# Uni-2_1_Complete.net
KiCad netlist of a schematic drawn in EAGLE
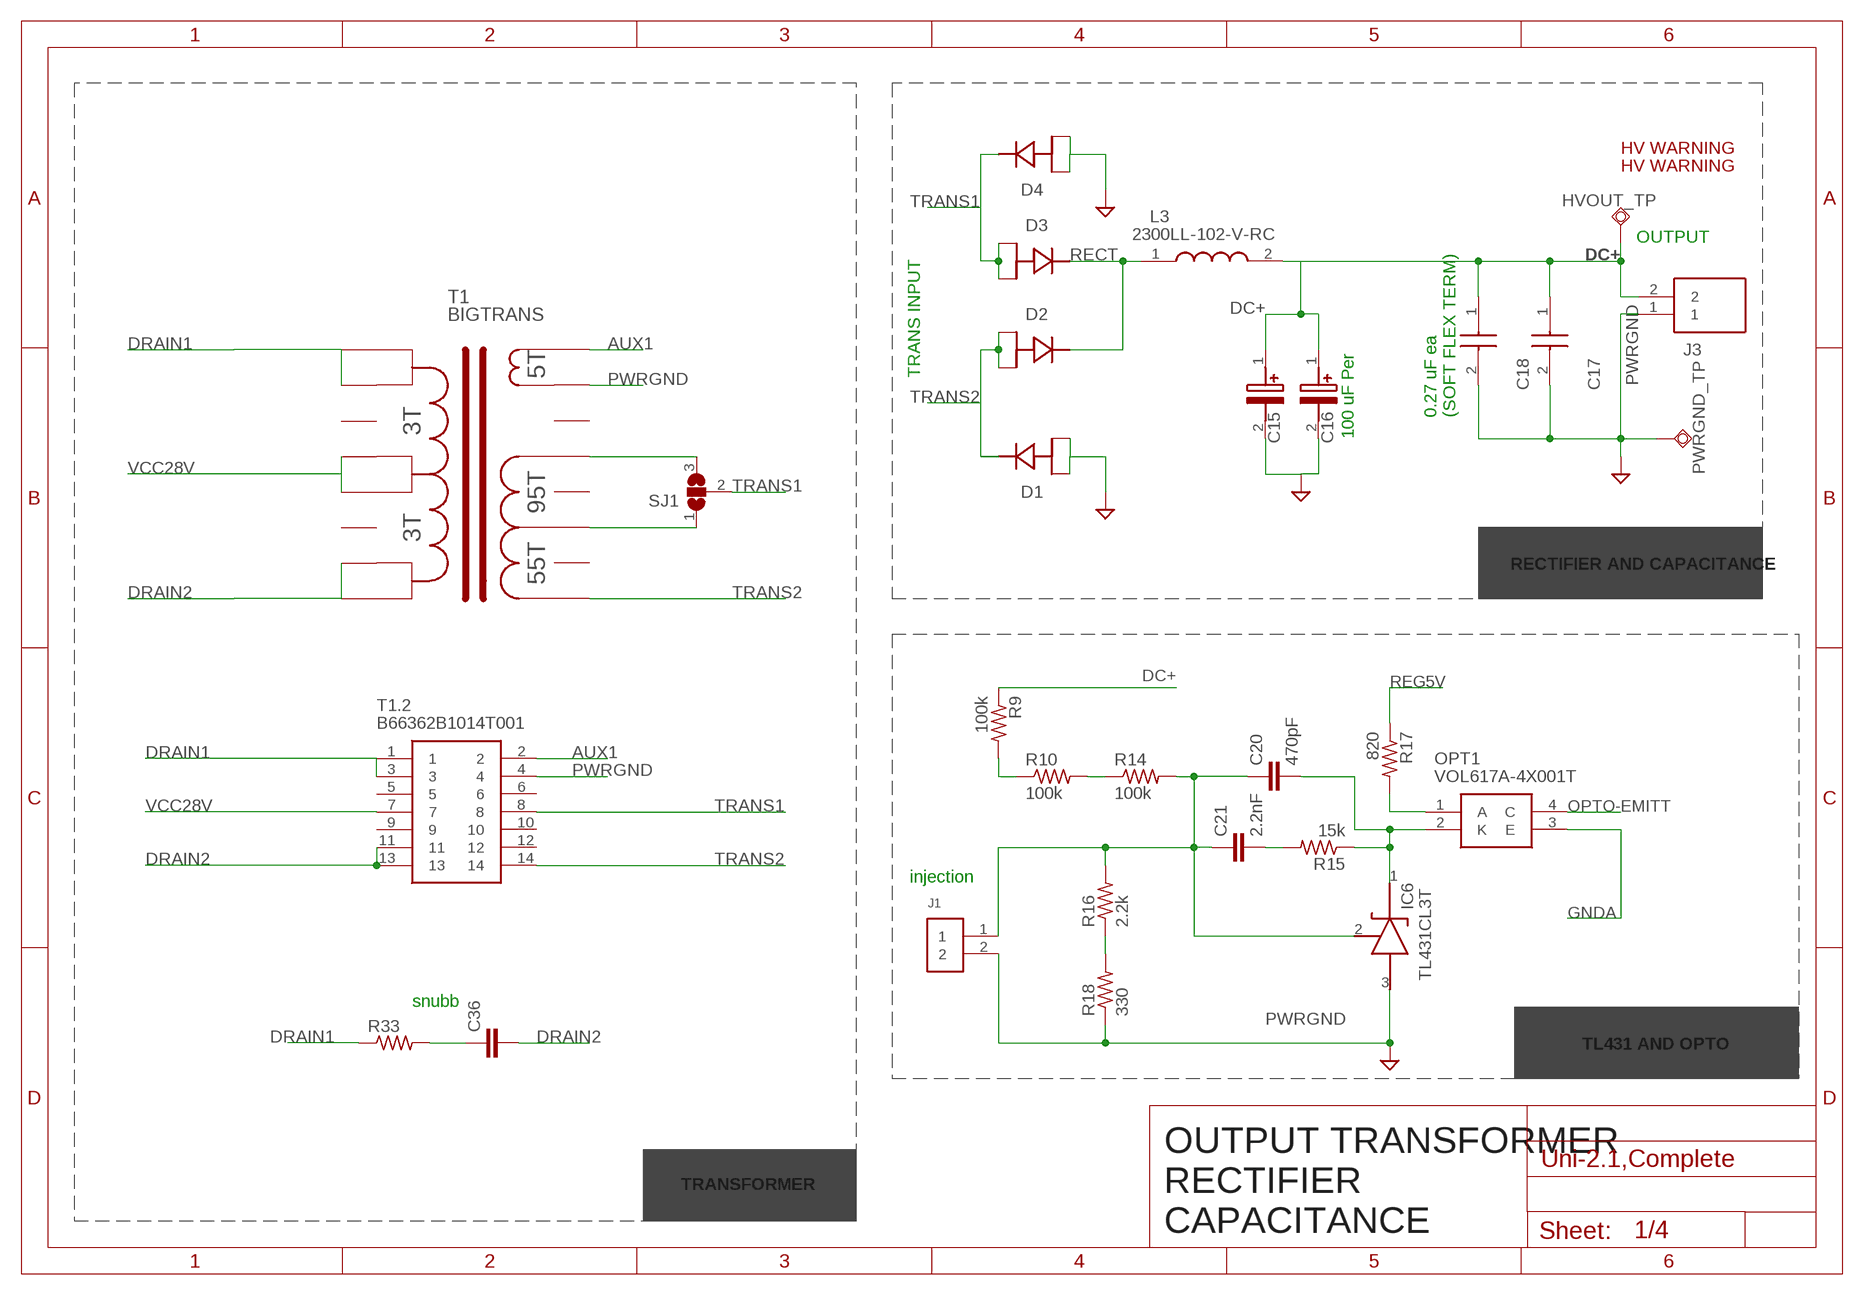
[diagram p0: schematic, sheet 1]
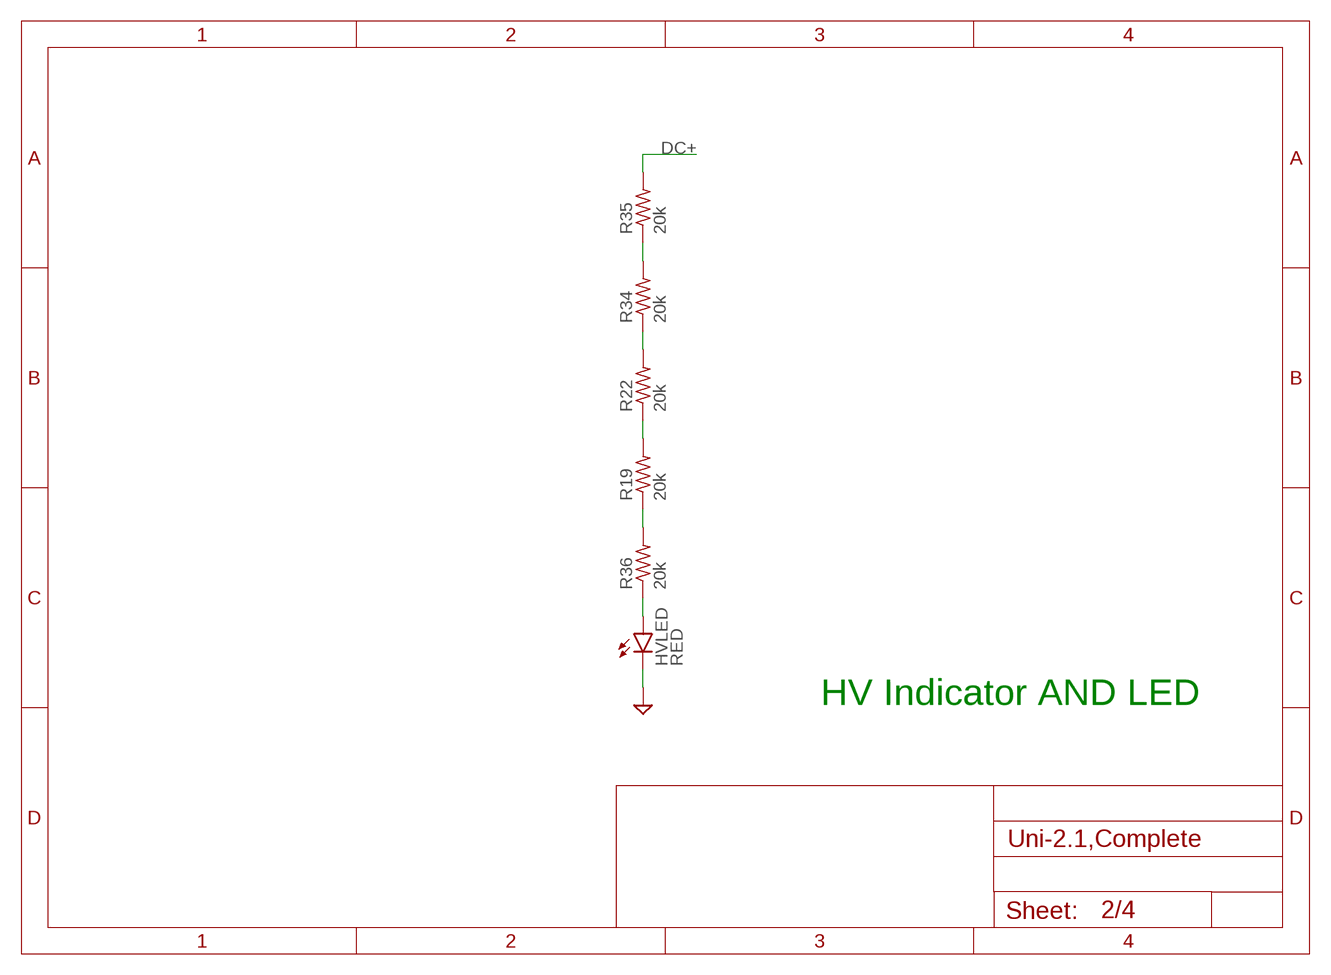
[diagram p1: schematic, sheet 2]
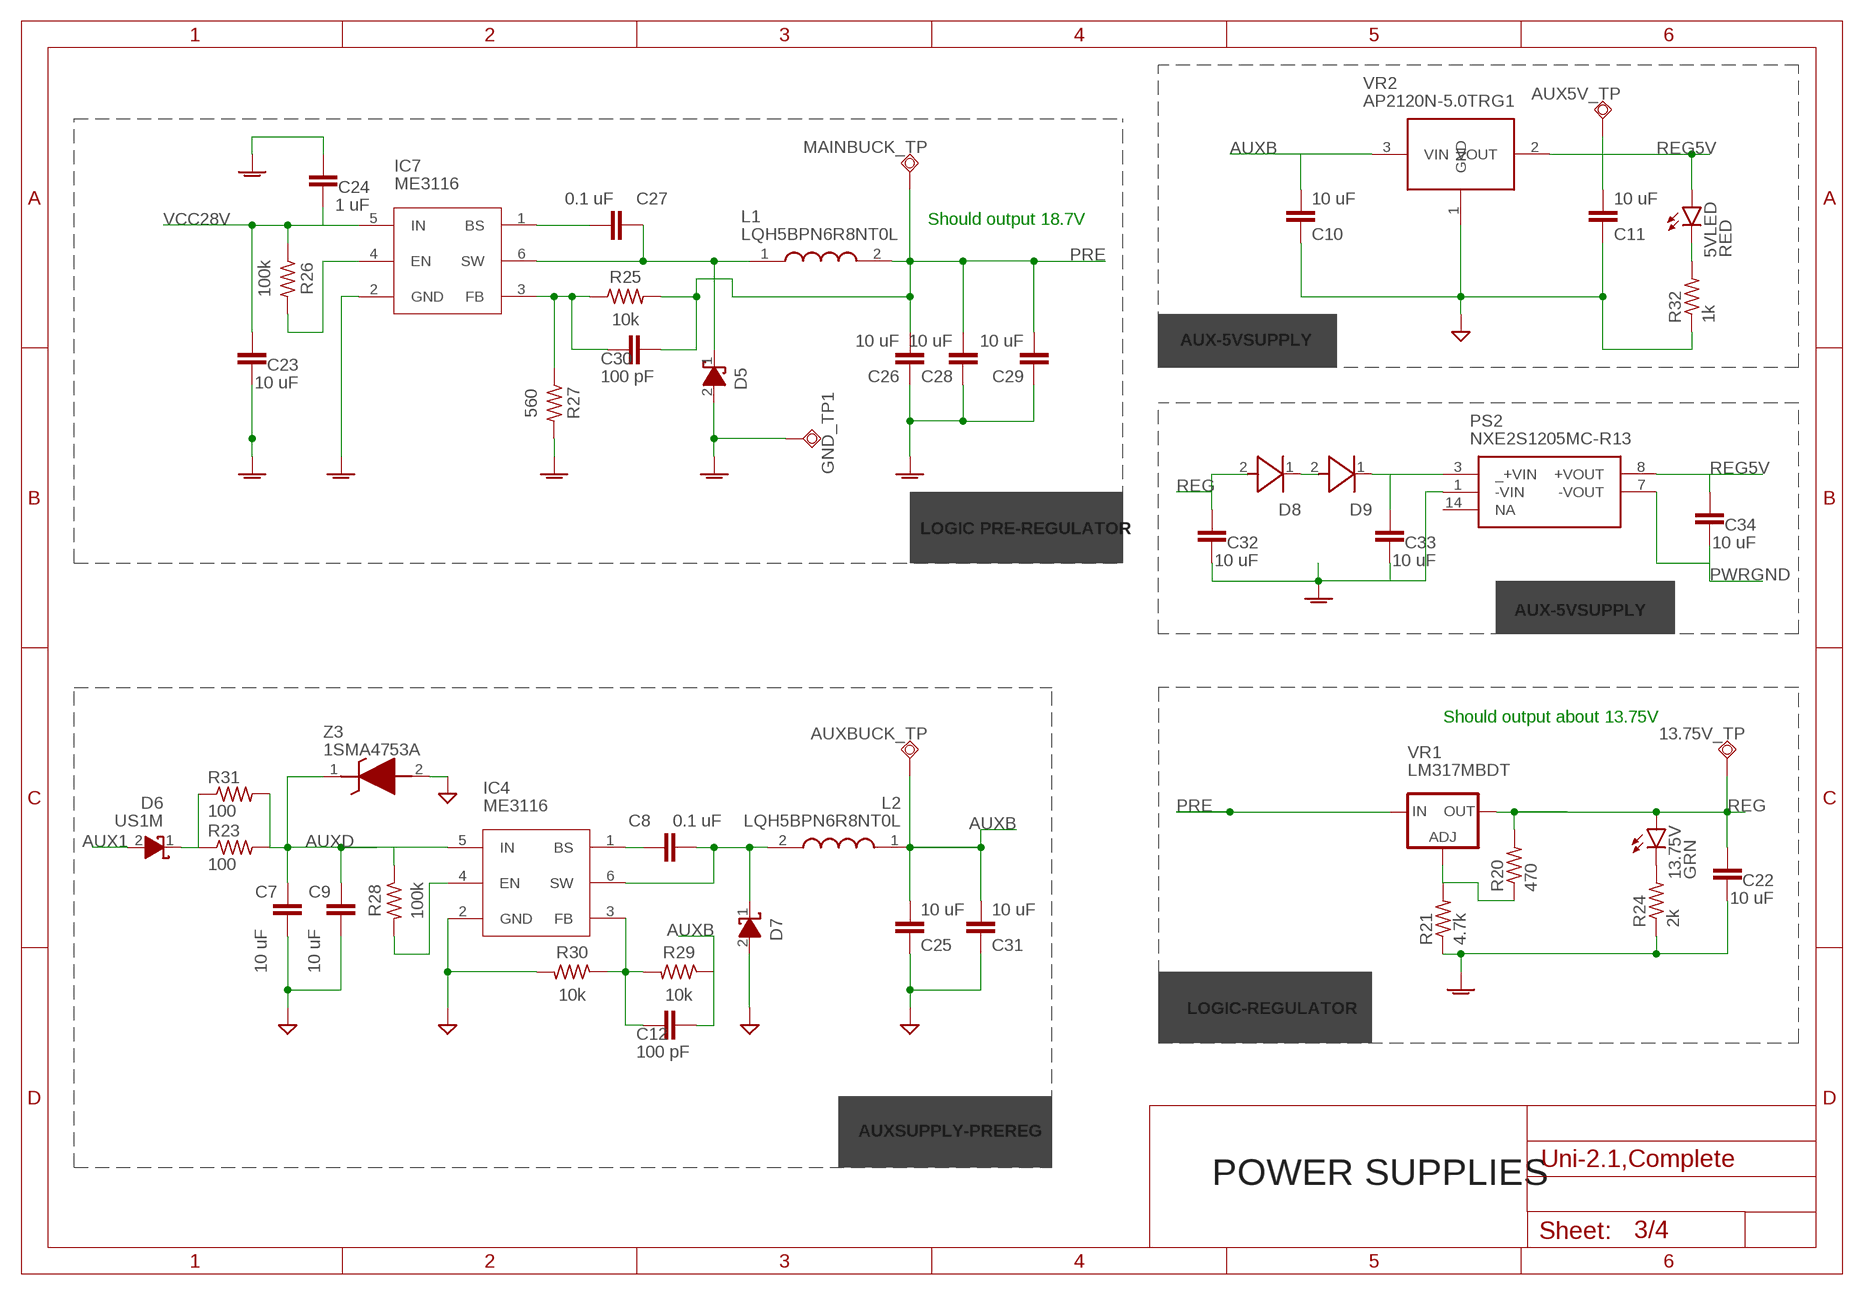
[diagram p2: schematic, sheet 3]
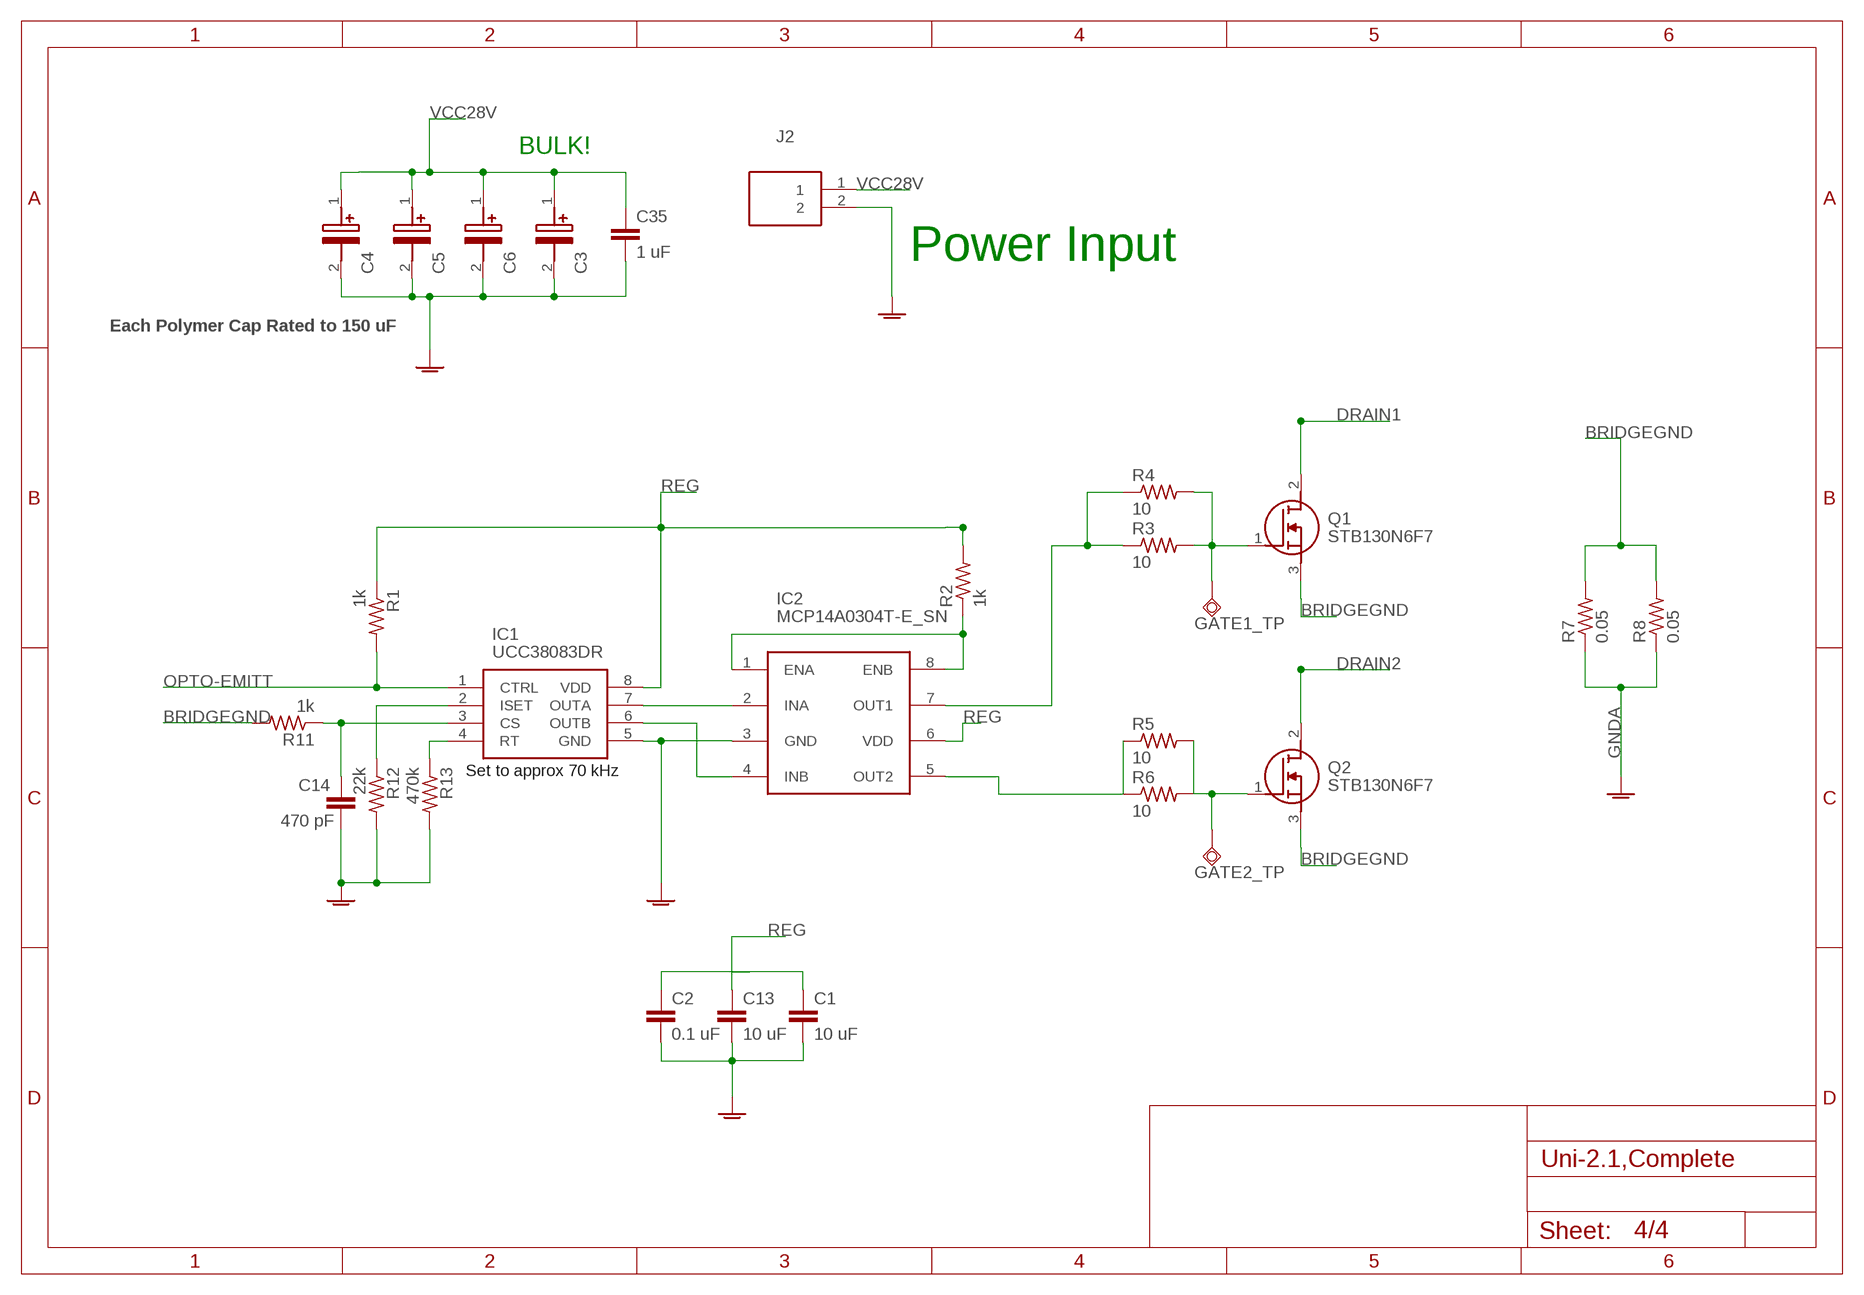
[diagram p3: schematic, sheet 4]

(export (version "E")
  (design (tool "Eeschema 10.0.6"))
  (components
    (comp (ref "C1")
      (value "10 uF")
      (footprint "eagle-import:C0603K")
      (fields (field (name "LCSC_PART") "C440198"))
      (libsource (lib "eagle-import") (part "rcl_334_C-EUC0603K"))
    )
    (comp (ref "C2")
      (value "0.1 uF")
      (footprint "eagle-import:C0603K")
      (fields (field (name "LCSC_PART") "C440198"))
      (libsource (lib "eagle-import") (part "rcl_334_C-EUC0603K"))
    )
    (comp (ref "C3")
      (value "OVK151M1VTR-10131")
      (footprint "eagle-import:16SVF1000M")
      (libsource (lib "eagle-import") (part "OVK151M1VTR-10131"))
    )
    (comp (ref "C4")
      (value "OVK151M1VTR-10131")
      (footprint "eagle-import:16SVF1000M")
      (libsource (lib "eagle-import") (part "OVK151M1VTR-10131"))
    )
    (comp (ref "C5")
      (value "OVK151M1VTR-10131")
      (footprint "eagle-import:16SVF1000M")
      (libsource (lib "eagle-import") (part "OVK151M1VTR-10131"))
    )
    (comp (ref "C6")
      (value "OVK151M1VTR-10131")
      (footprint "eagle-import:16SVF1000M")
      (libsource (lib "eagle-import") (part "OVK151M1VTR-10131"))
    )
    (comp (ref "C13")
      (value "10 uF")
      (footprint "eagle-import:C0603K")
      (fields (field (name "LCSC_PART") "C440198"))
      (libsource (lib "eagle-import") (part "rcl_334_C-EUC0603K"))
    )
    (comp (ref "C14")
      (value "470 pF")
      (footprint "eagle-import:C0603K")
      (fields (field (name "LCSC_PART") "C1620"))
      (libsource (lib "eagle-import") (part "rcl_334_C-EUC0603K"))
    )
    (comp (ref "C35")
      (value "1 uF")
      (footprint "eagle-import:C0805K")
      (fields (field (name "LCSC_PART") "C440198"))
      (libsource (lib "eagle-import") (part "rcl_334_C-EUC0805K"))
    )
    (comp (ref "GATE1_TP")
      (value "TPSQPAD1-17")
      (footprint "eagle-import:P1-17")
      (libsource (lib "eagle-import") (part "TPSQPAD1-17"))
    )
    (comp (ref "GATE2_TP")
      (value "TPSQPAD1-17")
      (footprint "eagle-import:P1-17")
      (libsource (lib "eagle-import") (part "TPSQPAD1-17"))
    )
    (comp (ref "IC1")
      (value "UCC38083DR")
      (footprint "eagle-import:SOIC127P600X175-8N")
      (fields (field (name "MOUSER_PART_NUMBER") "595-UCC38083DR"))
      (libsource (lib "eagle-import") (part "UCC38083DR"))
    )
    (comp (ref "IC2")
      (value "MCP14A0304T-E_SN")
      (footprint "eagle-import:SOIC127P600X175-8N")
      (fields
        (field (name "MANUFACTURER_PART_NUMBER") "MCP14A0304T-E/SN")
        (field (name "MOUSER_PART_NUMBER") "579-MCP14A0304T-E/SN")
      )
      (libsource (lib "eagle-import") (part "MCP14A0304T-E_SN"))
    )
    (comp (ref "J2")
      (value "TB005-762-02BE")
      (footprint "eagle-import:TB00576202BE")
      (fields (field (name "MOUSER_PART_NUMBER") "490-TB005-762-02BE"))
      (libsource (lib "eagle-import") (part "TB005-762-02BE"))
    )
    (comp (ref "Q1")
      (value "STB130N6F7")
      (footprint "eagle-import:D2PAK")
      (libsource (lib "eagle-import") (part "STB130N6F7"))
    )
    (comp (ref "Q2")
      (value "STB130N6F7")
      (footprint "eagle-import:D2PAK")
      (libsource (lib "eagle-import") (part "STB130N6F7"))
    )
    (comp (ref "R1")
      (value "1k")
      (footprint "eagle-import:R0603")
      (fields (field (name "LCSC_PART") "C22975"))
      (libsource (lib "eagle-import") (part "R-US_R0603"))
    )
    (comp (ref "R2")
      (value "1k")
      (footprint "eagle-import:R0402")
      (libsource (lib "eagle-import") (part "R-US_R0402"))
    )
    (comp (ref "R3")
      (value "10")
      (footprint "eagle-import:R0805")
      (libsource (lib "eagle-import") (part "R-US_R0805"))
    )
    (comp (ref "R4")
      (value "10")
      (footprint "eagle-import:R0805")
      (libsource (lib "eagle-import") (part "R-US_R0805"))
    )
    (comp (ref "R5")
      (value "10")
      (footprint "eagle-import:R0805")
      (libsource (lib "eagle-import") (part "R-US_R0805"))
    )
    (comp (ref "R6")
      (value "10")
      (footprint "eagle-import:R0805")
      (libsource (lib "eagle-import") (part "R-US_R0805"))
    )
    (comp (ref "R7")
      (value "0.05")
      (footprint "eagle-import:R2512")
      (libsource (lib "eagle-import") (part "R-US_R2512"))
    )
    (comp (ref "R8")
      (value "0.05")
      (footprint "eagle-import:R2512")
      (libsource (lib "eagle-import") (part "R-US_R2512"))
    )
    (comp (ref "R11")
      (value "1k")
      (footprint "eagle-import:R0603")
      (fields (field (name "LCSC_PART") "C21190"))
      (libsource (lib "eagle-import") (part "R-US_R0603"))
    )
    (comp (ref "R12")
      (value "22k")
      (footprint "eagle-import:R0603")
      (fields (field (name "LCSC_PART") "C31850"))
      (libsource (lib "eagle-import") (part "R-US_R0603"))
    )
    (comp (ref "R13")
      (value "470k")
      (footprint "eagle-import:R0603")
      (fields (field (name "LCSC_PART") "C25811"))
      (libsource (lib "eagle-import") (part "R-US_R0603"))
    )
    (comp (ref "5VLED")
      (value "RED")
      (footprint "eagle-import:CHIPLED_0805")
      (fields (field (name "LCSC_PART") "C72043"))
      (libsource (lib "eagle-import") (part "LEDCHIPLED_0805"))
    )
    (comp (ref "13.75V")
      (value "GRN")
      (footprint "eagle-import:CHIPLED_0805")
      (fields (field (name "LCSC_PART") "C72043"))
      (libsource (lib "eagle-import") (part "LEDCHIPLED_0805"))
    )
    (comp (ref "13.75V_TP")
      (value "TPSQPAD1-17")
      (footprint "eagle-import:P1-17")
      (libsource (lib "eagle-import") (part "TPSQPAD1-17"))
    )
    (comp (ref "AUX5V_TP")
      (value "TPSQPAD1-17")
      (footprint "eagle-import:P1-17")
      (libsource (lib "eagle-import") (part "TPSQPAD1-17"))
    )
    (comp (ref "AUXBUCK_TP")
      (value "TPSQPAD1-17")
      (footprint "eagle-import:P1-17")
      (libsource (lib "eagle-import") (part "TPSQPAD1-17"))
    )
    (comp (ref "C7")
      (value "10 uF")
      (footprint "eagle-import:C0805K")
      (libsource (lib "eagle-import") (part "rcl_334_C-EUC0805K"))
    )
    (comp (ref "C8")
      (value "0.1 uF")
      (footprint "eagle-import:C0603K")
      (fields (field (name "LCSC_PART") "C14663"))
      (libsource (lib "eagle-import") (part "rcl_334_C-EUC0603K"))
    )
    (comp (ref "C9")
      (value "10 uF")
      (footprint "eagle-import:C0805K")
      (libsource (lib "eagle-import") (part "rcl_334_C-EUC0805K"))
    )
    (comp (ref "C10")
      (value "10 uF")
      (footprint "eagle-import:C0603K")
      (fields (field (name "LCSC_PART") "C440198"))
      (libsource (lib "eagle-import") (part "rcl_334_C-EUC0603K"))
    )
    (comp (ref "C11")
      (value "10 uF")
      (footprint "eagle-import:C0603K")
      (libsource (lib "eagle-import") (part "rcl_334_C-EUC0603K"))
    )
    (comp (ref "C12")
      (value "100 pF")
      (footprint "eagle-import:C0402K")
      (fields (field (name "LCSC_PART") "C1546"))
      (libsource (lib "eagle-import") (part "rcl_334_C-EUC0402K"))
    )
    (comp (ref "C22")
      (value "10 uF")
      (footprint "eagle-import:C0805K")
      (fields (field (name "LCSC_PART") "C440198"))
      (libsource (lib "eagle-import") (part "C-EUC0805K"))
    )
    (comp (ref "C23")
      (value "10 uF")
      (footprint "eagle-import:C0805K")
      (fields (field (name "LCSC_PART") "C440198"))
      (libsource (lib "eagle-import") (part "C-EUC0805K"))
    )
    (comp (ref "C24")
      (value "1 uF")
      (footprint "eagle-import:C0603K")
      (fields (field (name "LCSC_PART") "C440198"))
      (libsource (lib "eagle-import") (part "rcl_334_C-EUC0603K"))
    )
    (comp (ref "C25")
      (value "10 uF")
      (footprint "eagle-import:C0603K")
      (fields (field (name "LCSC_PART") "C440198"))
      (libsource (lib "eagle-import") (part "rcl_334_C-EUC0603K"))
    )
    (comp (ref "C26")
      (value "10 uF")
      (footprint "eagle-import:C0805K")
      (fields (field (name "LCSC_PART") "C440198"))
      (libsource (lib "eagle-import") (part "C-EUC0805K"))
    )
    (comp (ref "C27")
      (value "0.1 uF")
      (footprint "eagle-import:C0603K")
      (fields (field (name "LCSC_PART") "C14663"))
      (libsource (lib "eagle-import") (part "rcl_334_C-EUC0603K"))
    )
    (comp (ref "C28")
      (value "10 uF")
      (footprint "eagle-import:C0805K")
      (fields (field (name "LCSC_PART") "C440198"))
      (libsource (lib "eagle-import") (part "C-EUC0805K"))
    )
    (comp (ref "C29")
      (value "10 uF")
      (footprint "eagle-import:C0805K")
      (fields (field (name "LCSC_PART") "C440198"))
      (libsource (lib "eagle-import") (part "C-EUC0805K"))
    )
    (comp (ref "C30")
      (value "100 pF")
      (footprint "eagle-import:C0402K")
      (fields (field (name "LCSC_PART") "C1546"))
      (libsource (lib "eagle-import") (part "rcl_334_C-EUC0402K"))
    )
    (comp (ref "C31")
      (value "10 uF")
      (footprint "eagle-import:C0402")
      (fields (field (name "LCSC_PART") "C440198"))
      (libsource (lib "eagle-import") (part "rcl_334_C-EUC0402"))
    )
    (comp (ref "C32")
      (value "10 uF")
      (footprint "eagle-import:C0805K")
      (fields (field (name "LCSC_PART") "C440198"))
      (libsource (lib "eagle-import") (part "C-EUC0805K"))
    )
    (comp (ref "C33")
      (value "10 uF")
      (footprint "eagle-import:C0603K")
      (fields (field (name "LCSC_PART") "C440198"))
      (libsource (lib "eagle-import") (part "rcl_334_C-EUC0603K"))
    )
    (comp (ref "C34")
      (value "10 uF")
      (footprint "eagle-import:C0603K")
      (fields (field (name "LCSC_PART") "C440198"))
      (libsource (lib "eagle-import") (part "rcl_334_C-EUC0603K"))
    )
    (comp (ref "D5")
      (value "SCHOTTKY")
      (footprint "eagle-import:DIOM5127X229N")
      (fields
        (field (name "MANUFACTURER_PART_NUMBER") "SS16HE3_B/H")
        (field (name "MOUSER_PART_NUMBER") "78-SS16HE3_B/H")
        (field (name "LCSC_PART") "C22452")
      )
      (libsource (lib "eagle-import") (part "SCHOTTKY"))
    )
    (comp (ref "D6")
      (value "US1M")
      (footprint "eagle-import:DIOM5127X229N")
      (fields
        (field (name "MANUFACTURER_PART_NUMBER") "SS16HE3_B/H")
        (field (name "MOUSER_PART_NUMBER") "78-SS16HE3_B/H")
      )
      (libsource (lib "eagle-import") (part "SCHOTTKY"))
    )
    (comp (ref "D7")
      (value "SCHOTTKY")
      (footprint "eagle-import:DIOM5127X229N")
      (fields
        (field (name "MANUFACTURER_PART_NUMBER") "SS16HE3_B/H")
        (field (name "MOUSER_PART_NUMBER") "78-SS16HE3_B/H")
        (field (name "LCSC_PART") "C22452")
      )
      (libsource (lib "eagle-import") (part "SCHOTTKY"))
    )
    (comp (ref "D8")
      (value "SM4007PL")
      (footprint "eagle-import:SOD3716X145N")
      (fields
        (field (name "MANUFACTURER_PART_NUMBER") "1N4148W-7-F")
        (field (name "MOUSER_PART_NUMBER") "621-1N4148W-F")
        (field (name "LCSC_PART") "C64898")
      )
      (libsource (lib "eagle-import") (part "1N4148W-7-F"))
    )
    (comp (ref "D9")
      (value "SM4007PL")
      (footprint "eagle-import:SOD3716X145N")
      (fields
        (field (name "MANUFACTURER_PART_NUMBER") "1N4148W-7-F")
        (field (name "MOUSER_PART_NUMBER") "621-1N4148W-F")
        (field (name "LCSC_PART") "C64898")
      )
      (libsource (lib "eagle-import") (part "1N4148W-7-F"))
    )
    (comp (ref "GND_TP1")
      (value "TPSQPAD1-13")
      (footprint "eagle-import:P1-13")
      (libsource (lib "eagle-import") (part "TPSQPAD1-13"))
    )
    (comp (ref "IC4")
      (value "ME3116")
      (footprint "eagle-import:SOT95P280X100-6N")
      (fields (field (name "LCSC_PART") "C97643"))
      (libsource (lib "eagle-import") (part "ME3116"))
    )
    (comp (ref "IC7")
      (value "ME3116")
      (footprint "eagle-import:SOT95P280X100-6N")
      (fields (field (name "LCSC_PART") "C97643"))
      (libsource (lib "eagle-import") (part "ME3116"))
    )
    (comp (ref "L1")
      (value "LQH5BPN6R8NT0L")
      (footprint "eagle-import:LQH5BPB100MT0L")
      (fields (field (name "MOUSER_PART_NUMBER") "81-LQH5BPN6R8NT0L0L"))
      (libsource (lib "eagle-import") (part "LQH5BPN6R8NT0L"))
    )
    (comp (ref "L2")
      (value "LQH5BPN6R8NT0L")
      (footprint "eagle-import:LQH5BPB100MT0L")
      (fields (field (name "MOUSER_PART_NUMBER") "81-LQH5BPN6R8NT0L0L"))
      (libsource (lib "eagle-import") (part "LQH5BPN6R8NT0L"))
    )
    (comp (ref "MAINBUCK_TP")
      (value "TPSQPAD1-17")
      (footprint "eagle-import:P1-17")
      (libsource (lib "eagle-import") (part "TPSQPAD1-17"))
    )
    (comp (ref "PS2")
      (value "NXE2S1205MC-R13")
      (footprint "eagle-import:NXE2S1205MCR13")
      (fields (field (name "MOUSER_PART_NUMBER") "580-NXE2S1205MC-R13"))
      (libsource (lib "eagle-import") (part "NXE2S1205MC-R13"))
    )
    (comp (ref "R20")
      (value "470")
      (footprint "eagle-import:R0603")
      (fields (field (name "LCSC_PART") "C22975"))
      (libsource (lib "eagle-import") (part "R-US_R0603"))
    )
    (comp (ref "R21")
      (value "4.7k")
      (footprint "eagle-import:R0603")
      (fields (field (name "LCSC_PART") "C22975"))
      (libsource (lib "eagle-import") (part "R-US_R0603"))
    )
    (comp (ref "R23")
      (value "100")
      (footprint "eagle-import:R1206")
      (libsource (lib "eagle-import") (part "R-US_R1206"))
    )
    (comp (ref "R24")
      (value "2k")
      (footprint "eagle-import:R0603")
      (fields (field (name "LCSC_PART") "C22975"))
      (libsource (lib "eagle-import") (part "R-US_R0603"))
    )
    (comp (ref "R25")
      (value "10k")
      (footprint "eagle-import:R0402")
      (fields (field (name "LCSC_PART") "C25779"))
      (libsource (lib "eagle-import") (part "R-US_R0402"))
    )
    (comp (ref "R26")
      (value "100k")
      (footprint "eagle-import:R0402")
      (fields (field (name "LCSC_PART") "C25741") (field (name "SPICEPREFIX") "R"))
      (libsource (lib "eagle-import") (part "R-US_R0402"))
    )
    (comp (ref "R27")
      (value "560")
      (footprint "eagle-import:R0402")
      (fields (field (name "LCSC_PART") "C4177") (field (name "SPICEPREFIX") "R"))
      (libsource (lib "eagle-import") (part "R-US_R0402"))
    )
    (comp (ref "R28")
      (value "100k")
      (footprint "eagle-import:R0402")
      (fields (field (name "LCSC_PART") "C25741") (field (name "SPICEPREFIX") "R"))
      (libsource (lib "eagle-import") (part "R-US_R0402"))
    )
    (comp (ref "R29")
      (value "10k")
      (footprint "eagle-import:R0402")
      (fields (field (name "LCSC_PART") "C25779"))
      (libsource (lib "eagle-import") (part "R-US_R0402"))
    )
    (comp (ref "R30")
      (value "10k")
      (footprint "eagle-import:R0402")
      (fields (field (name "LCSC_PART") "C25779"))
      (libsource (lib "eagle-import") (part "R-US_R0402"))
    )
    (comp (ref "R31")
      (value "100")
      (footprint "eagle-import:R1206")
      (libsource (lib "eagle-import") (part "R-US_R1206"))
    )
    (comp (ref "R32")
      (value "1k")
      (footprint "eagle-import:R0603")
      (fields (field (name "LCSC_PART") "C22975"))
      (libsource (lib "eagle-import") (part "R-US_R0603"))
    )
    (comp (ref "VR1")
      (value "LM317MBDT")
      (footprint "eagle-import:DPACK")
      (libsource (lib "eagle-import") (part "LM317?MBDT"))
    )
    (comp (ref "VR2")
      (value "AP2120N-5.0TRG1")
      (footprint "eagle-import:SOT95P240X120-3N")
      (fields (field (name "MOUSER_PART_NUMBER") "621-AP2120N-5.0TRG1"))
      (libsource (lib "eagle-import") (part "AP2120N-5.0TRG1"))
    )
    (comp (ref "Z3")
      (value "1SMA4753A")
      (footprint "eagle-import:DIOM5226X220N")
      (fields
        (field (name "MANUFACTURER_PART_NUMBER") "1SMA5942BT3G")
        (field (name "MOUSER_PART_NUMBER") "863-1SMA5942BT3G")
        (field (name "LCSC_PART") "C362284")
      )
      (libsource (lib "eagle-import") (part "1SMA5942BT3G"))
    )
    (comp (ref "C15")
      (value "400BXW100MEFR18X25")
      (footprint "eagle-import:CAPPRD750W80D1825H2700")
      (libsource (lib "eagle-import") (part "400BXW100MEFR18X25"))
    )
    (comp (ref "C16")
      (value "400BXW100MEFR18X25")
      (footprint "eagle-import:CAPPRD750W80D1825H2700")
      (libsource (lib "eagle-import") (part "400BXW100MEFR18X25"))
    )
    (comp (ref "C17")
      (value "C1812C274KCRACAUTO")
      (footprint "eagle-import:C1812")
      (fields (field (name "MOUSER_PART_NUMBER") "80-C1812C274KCRAUTO"))
      (libsource (lib "eagle-import") (part "C1812C274KCRACAUTO"))
    )
    (comp (ref "C18")
      (value "C1812C274KCRACAUTO")
      (footprint "eagle-import:C1812")
      (fields (field (name "MOUSER_PART_NUMBER") "80-C1812C274KCRAUTO"))
      (libsource (lib "eagle-import") (part "C1812C274KCRACAUTO"))
    )
    (comp (ref "C20")
      (value "470pF")
      (footprint "eagle-import:C0603K")
      (libsource (lib "eagle-import") (part "rcl_334_C-EUC0603K"))
    )
    (comp (ref "C21")
      (value "2.2nF")
      (footprint "eagle-import:C0603K")
      (libsource (lib "eagle-import") (part "rcl_334_C-EUC0603K"))
    )
    (comp (ref "C36")
      (value "C-EUC1210K")
      (footprint "eagle-import:C1210K")
      (libsource (lib "eagle-import") (part "rcl_334_C-EUC1210K"))
    )
    (comp (ref "D1")
      (value "FERD20H60CG-TR")
      (footprint "eagle-import:STB20N95K5")
      (fields (field (name "MOUSER_PART_NUMBER") "511-FERD20H60CG-TR"))
      (libsource (lib "eagle-import") (part "FERD20H60CG-TR"))
    )
    (comp (ref "D2")
      (value "FERD20H60CG-TR")
      (footprint "eagle-import:STB20N95K5")
      (fields (field (name "MOUSER_PART_NUMBER") "511-FERD20H60CG-TR"))
      (libsource (lib "eagle-import") (part "FERD20H60CG-TR"))
    )
    (comp (ref "D3")
      (value "FERD20H60CG-TR")
      (footprint "eagle-import:STB20N95K5")
      (fields (field (name "MOUSER_PART_NUMBER") "511-FERD20H60CG-TR"))
      (libsource (lib "eagle-import") (part "FERD20H60CG-TR"))
    )
    (comp (ref "D4")
      (value "FERD20H60CG-TR")
      (footprint "eagle-import:STB20N95K5")
      (fields (field (name "MOUSER_PART_NUMBER") "511-FERD20H60CG-TR"))
      (libsource (lib "eagle-import") (part "FERD20H60CG-TR"))
    )
    (comp (ref "HVOUT_TP")
      (value "TPSQPAD1-13")
      (footprint "eagle-import:P1-13")
      (libsource (lib "eagle-import") (part "TPSQPAD1-13"))
    )
    (comp (ref "IC6")
      (value "TL431CL3T")
      (footprint "eagle-import:SOT95P237X112-3N")
      (fields (field (name "MOUSER_PART_NUMBER") "511-TL431CL3T"))
      (libsource (lib "eagle-import") (part "TL431CL3T"))
    )
    (comp (ref "J1")
      (value "61300211121")
      (footprint "eagle-import:61300211121")
      (fields
        (field (name "DIGI_KEY_PART_NUMBER") "732-5315-ND")
        (field (name "MANUFACTURER") "Wurth Electronics Inc.")
        (field (name "CREATED_BY") "PCBLayout.com")
      )
      (libsource (lib "eagle-import") (part "61300211121"))
    )
    (comp (ref "J3")
      (value "TB005-762-02BE")
      (footprint "eagle-import:TB00576202BE")
      (fields (field (name "MOUSER_PART_NUMBER") "490-TB005-762-02BE"))
      (libsource (lib "eagle-import") (part "TB005-762-02BE"))
    )
    (comp (ref "L3")
      (value "2300LL-102-V-RC")
      (footprint "eagle-import:2300LL102VRC")
      (fields (field (name "MOUSER_PART_NUMBER") "652-2300LL-102-V-RC"))
      (libsource (lib "eagle-import") (part "2300LL-102-V-RC"))
    )
    (comp (ref "OPT1")
      (value "VOL617A-4X001T")
      (footprint "eagle-import:SOP254P1015X230-4N")
      (fields (field (name "MOUSER_PART_NUMBER") "78-VOL617A-4X001T"))
      (libsource (lib "eagle-import") (part "VOL617A-4X001T"))
    )
    (comp (ref "PWRGND_TP")
      (value "TPSQPAD1-13")
      (footprint "eagle-import:P1-13")
      (libsource (lib "eagle-import") (part "TPSQPAD1-13"))
    )
    (comp (ref "R9")
      (value "100k")
      (footprint "eagle-import:R1206")
      (libsource (lib "eagle-import") (part "R-US_R1206"))
    )
    (comp (ref "R10")
      (value "100k")
      (footprint "eagle-import:R1206")
      (libsource (lib "eagle-import") (part "R-US_R1206"))
    )
    (comp (ref "R14")
      (value "100k")
      (footprint "eagle-import:R1206")
      (libsource (lib "eagle-import") (part "R-US_R1206"))
    )
    (comp (ref "R15")
      (value "15k")
      (footprint "eagle-import:R0603")
      (libsource (lib "eagle-import") (part "R-US_R0603"))
    )
    (comp (ref "R16")
      (value "2.2k")
      (footprint "eagle-import:R0805")
      (libsource (lib "eagle-import") (part "R-US_R0805"))
    )
    (comp (ref "R17")
      (value "820")
      (footprint "eagle-import:R0603")
      (libsource (lib "eagle-import") (part "R-US_R0603"))
    )
    (comp (ref "R18")
      (value "330")
      (footprint "eagle-import:R0805")
      (libsource (lib "eagle-import") (part "R-US_R0805"))
    )
    (comp (ref "R33")
      (value "R-US_R1206")
      (footprint "eagle-import:R1206")
      (libsource (lib "eagle-import") (part "R-US_R1206"))
    )
    (comp (ref "SJ1")
      (value "SJ2WW")
      (footprint "eagle-import:SJ_2W")
      (libsource (lib "eagle-import") (part "SJ2WW"))
    )
    (comp (ref "T1")
      (value "BIGTRANS")
      (footprint "eagle-import:BIGTRANS!")
      (libsource (lib "eagle-import") (part "BIGTRANS"))
    )
    (comp (ref "T1.2")
      (value "B66362B1014T001")
      (footprint "eagle-import:B66362B1014T001")
      (fields (field (name "MOUSER_PART_NUMBER") "871-B66362B1014T001"))
      (libsource (lib "eagle-import") (part "B66362B1014T001"))
    )
    (comp (ref "U$2")
      (value "HV")
      (footprint "eagle-import:PSFBC_ELECTRIC_SHOCK")
      (libsource (lib "eagle-import") (part "HV"))
    )
    (comp (ref "U$3")
      (value "HV")
      (footprint "eagle-import:PSFBC_ELECTRIC_SHOCK")
      (libsource (lib "eagle-import") (part "HV"))
    )
    (comp (ref "HVLED")
      (value "RED")
      (footprint "eagle-import:CHIPLED_0805")
      (libsource (lib "eagle-import") (part "LEDCHIPLED_0805"))
    )
    (comp (ref "R19")
      (value "20k")
      (footprint "eagle-import:R1206")
      (libsource (lib "eagle-import") (part "R-US_R1206"))
    )
    (comp (ref "R22")
      (value "20k")
      (footprint "eagle-import:R1206")
      (libsource (lib "eagle-import") (part "R-US_R1206"))
    )
    (comp (ref "R34")
      (value "20k")
      (footprint "eagle-import:R1206")
      (libsource (lib "eagle-import") (part "R-US_R1206"))
    )
    (comp (ref "R35")
      (value "20k")
      (footprint "eagle-import:R1206")
      (libsource (lib "eagle-import") (part "R-US_R1206"))
    )
    (comp (ref "R36")
      (value "20k")
      (footprint "eagle-import:R1206")
      (libsource (lib "eagle-import") (part "R-US_R1206"))
    )
  )
  (nets
    (net (code "1") (name "AUX1") (class "Default")
      (node (ref "D6") (pin "2") (pinfunction "A_2") (pintype "bidirectional"))
      (node (ref "T1") (pin "16") (pinfunction "16_16") (pintype "bidirectional"))
      (node (ref "T1.2") (pin "2") (pinfunction "2_2") (pintype "bidirectional"))
    )
    (net (code "2") (name "AUXB") (class "Default")
      (node (ref "AUXBUCK_TP") (pin "TP") (pinfunction "TP_TP") (pintype "input"))
      (node (ref "C10") (pin "2") (pinfunction "2_2") (pintype "passive"))
      (node (ref "C12") (pin "1") (pinfunction "1_1") (pintype "passive"))
      (node (ref "C25") (pin "2") (pinfunction "2_2") (pintype "passive"))
      (node (ref "C31") (pin "2") (pinfunction "2_2") (pintype "passive"))
      (node (ref "L2") (pin "1") (pinfunction "1_1") (pintype "bidirectional"))
      (node (ref "R29") (pin "1") (pinfunction "1_1") (pintype "passive"))
      (node (ref "VR2") (pin "3") (pinfunction "VIN_3") (pintype "bidirectional"))
    )
    (net (code "3") (name "AUXD") (class "Default")
      (node (ref "C7") (pin "1") (pinfunction "1_1") (pintype "passive"))
      (node (ref "C9") (pin "1") (pinfunction "1_1") (pintype "passive"))
      (node (ref "IC4") (pin "5") (pinfunction "IN_5") (pintype "bidirectional"))
      (node (ref "R23") (pin "2") (pinfunction "2_2") (pintype "passive"))
      (node (ref "R28") (pin "1") (pinfunction "1_1") (pintype "passive"))
      (node (ref "R31") (pin "2") (pinfunction "2_2") (pintype "passive"))
      (node (ref "Z3") (pin "1") (pinfunction "K_1") (pintype "bidirectional"))
    )
    (net (code "4") (name "BRIDGEGND") (class "Default")
      (node (ref "Q1") (pin "3") (pinfunction "S_3") (pintype "bidirectional"))
      (node (ref "Q2") (pin "3") (pinfunction "S_3") (pintype "bidirectional"))
      (node (ref "R11") (pin "2") (pinfunction "2_2") (pintype "passive"))
      (node (ref "R7") (pin "2") (pinfunction "2_2") (pintype "passive"))
      (node (ref "R8") (pin "2") (pinfunction "2_2") (pintype "passive"))
    )
    (net (code "5") (name "DC+") (class "Default")
      (node (ref "C15") (pin "1") (pinfunction "+_1") (pintype "bidirectional"))
      (node (ref "C16") (pin "1") (pinfunction "+_1") (pintype "bidirectional"))
      (node (ref "C17") (pin "1") (pinfunction "1_1") (pintype "bidirectional"))
      (node (ref "C18") (pin "1") (pinfunction "1_1") (pintype "bidirectional"))
      (node (ref "HVOUT_TP") (pin "TP") (pinfunction "TP_TP") (pintype "input"))
      (node (ref "J3") (pin "2") (pinfunction "2_2") (pintype "bidirectional"))
      (node (ref "L3") (pin "2") (pinfunction "2_2") (pintype "bidirectional"))
      (node (ref "R35") (pin "2") (pinfunction "2_2") (pintype "passive"))
      (node (ref "R9") (pin "1") (pinfunction "1_1") (pintype "passive"))
    )
    (net (code "6") (name "DRAIN1") (class "Default")
      (node (ref "Q1") (pin "2") (pinfunction "D_2") (pintype "bidirectional"))
      (node (ref "R33") (pin "1") (pinfunction "1_1") (pintype "passive"))
      (node (ref "T1") (pin "7") (pinfunction "7_7") (pintype "bidirectional"))
      (node (ref "T1") (pin "8") (pinfunction "8_8") (pintype "bidirectional"))
      (node (ref "T1.2") (pin "1") (pinfunction "1_1") (pintype "bidirectional"))
      (node (ref "T1.2") (pin "3") (pinfunction "3_3") (pintype "bidirectional"))
    )
    (net (code "7") (name "DRAIN2") (class "Default")
      (node (ref "C36") (pin "2") (pinfunction "2_2") (pintype "passive"))
      (node (ref "Q2") (pin "2") (pinfunction "D_2") (pintype "bidirectional"))
      (node (ref "T1") (pin "1") (pinfunction "1_1") (pintype "bidirectional"))
      (node (ref "T1") (pin "2") (pinfunction "2_2") (pintype "bidirectional"))
      (node (ref "T1.2") (pin "11") (pinfunction "11_11") (pintype "bidirectional"))
      (node (ref "T1.2") (pin "13") (pinfunction "13_13") (pintype "bidirectional"))
    )
    (net (code "8") (name "GNDA") (class "Default")
      (node (ref "C1") (pin "2") (pinfunction "2_2") (pintype "passive"))
      (node (ref "C13") (pin "2") (pinfunction "2_2") (pintype "passive"))
      (node (ref "C14") (pin "2") (pinfunction "2_2") (pintype "passive"))
      (node (ref "C2") (pin "2") (pinfunction "2_2") (pintype "passive"))
      (node (ref "C22") (pin "1") (pinfunction "1_1") (pintype "passive"))
      (node (ref "C23") (pin "1") (pinfunction "1_1") (pintype "passive"))
      (node (ref "C24") (pin "2") (pinfunction "2_2") (pintype "passive"))
      (node (ref "C26") (pin "1") (pinfunction "1_1") (pintype "passive"))
      (node (ref "C28") (pin "1") (pinfunction "1_1") (pintype "passive"))
      (node (ref "C29") (pin "1") (pinfunction "1_1") (pintype "passive"))
      (node (ref "C3") (pin "2") (pinfunction "-_2") (pintype "bidirectional"))
      (node (ref "C32") (pin "1") (pinfunction "1_1") (pintype "passive"))
      (node (ref "C33") (pin "1") (pinfunction "1_1") (pintype "passive"))
      (node (ref "C35") (pin "2") (pinfunction "2_2") (pintype "passive"))
      (node (ref "C4") (pin "2") (pinfunction "-_2") (pintype "bidirectional"))
      (node (ref "C5") (pin "2") (pinfunction "-_2") (pintype "bidirectional"))
      (node (ref "C6") (pin "2") (pinfunction "-_2") (pintype "bidirectional"))
      (node (ref "D5") (pin "2") (pinfunction "A_2") (pintype "bidirectional"))
      (node (ref "GND_TP1") (pin "TP") (pinfunction "TP_TP") (pintype "input"))
      (node (ref "IC1") (pin "5") (pinfunction "GND_5") (pintype "bidirectional"))
      (node (ref "IC2") (pin "3") (pinfunction "GND_3") (pintype "bidirectional"))
      (node (ref "IC7") (pin "2") (pinfunction "GND_2") (pintype "bidirectional"))
      (node (ref "J2") (pin "2") (pinfunction "2_2") (pintype "bidirectional"))
      (node (ref "OPT1") (pin "3") (pinfunction "E_3") (pintype "bidirectional"))
      (node (ref "PS2") (pin "1") (pinfunction "-VIN_1") (pintype "bidirectional"))
      (node (ref "R12") (pin "2") (pinfunction "2_2") (pintype "passive"))
      (node (ref "R13") (pin "2") (pinfunction "2_2") (pintype "passive"))
      (node (ref "R21") (pin "1") (pinfunction "1_1") (pintype "passive"))
      (node (ref "R24") (pin "1") (pinfunction "1_1") (pintype "passive"))
      (node (ref "R27") (pin "2") (pinfunction "2_2") (pintype "passive"))
      (node (ref "R7") (pin "1") (pinfunction "1_1") (pintype "passive"))
      (node (ref "R8") (pin "1") (pinfunction "1_1") (pintype "passive"))
    )
    (net (code "9") (name "Net-(5VLED-PadC)") (class "Default")
      (node (ref "5VLED") (pin "C") (pinfunction "C_C") (pintype "passive"))
      (node (ref "R32") (pin "2") (pinfunction "2_2") (pintype "passive"))
    )
    (net (code "10") (name "Net-(13.75V-PadC)") (class "Default")
      (node (ref "13.75V") (pin "C") (pinfunction "C_C") (pintype "passive"))
      (node (ref "R24") (pin "2") (pinfunction "2_2") (pintype "passive"))
    )
    (net (code "11") (name "Net-(C21-Pad2)") (class "Default")
      (node (ref "C21") (pin "2") (pinfunction "2_2") (pintype "passive"))
      (node (ref "R15") (pin "2") (pinfunction "2_2") (pintype "passive"))
    )
    (net (code "12") (name "Net-(C36-Pad1)") (class "Default")
      (node (ref "C36") (pin "1") (pinfunction "1_1") (pintype "passive"))
      (node (ref "R33") (pin "2") (pinfunction "2_2") (pintype "passive"))
    )
    (net (code "13") (name "Net-(D5-K)") (class "Default")
      (node (ref "C27") (pin "1") (pinfunction "1_1") (pintype "passive"))
      (node (ref "D5") (pin "1") (pinfunction "K_1") (pintype "bidirectional"))
      (node (ref "IC7") (pin "6") (pinfunction "SW_6") (pintype "bidirectional"))
      (node (ref "L1") (pin "1") (pinfunction "1_1") (pintype "bidirectional"))
    )
    (net (code "14") (name "Net-(D6-K)") (class "Default")
      (node (ref "D6") (pin "1") (pinfunction "K_1") (pintype "bidirectional"))
      (node (ref "R23") (pin "1") (pinfunction "1_1") (pintype "passive"))
      (node (ref "R31") (pin "1") (pinfunction "1_1") (pintype "passive"))
    )
    (net (code "15") (name "Net-(D7-K)") (class "Default")
      (node (ref "C8") (pin "2") (pinfunction "2_2") (pintype "passive"))
      (node (ref "D7") (pin "1") (pinfunction "K_1") (pintype "bidirectional"))
      (node (ref "IC4") (pin "6") (pinfunction "SW_6") (pintype "bidirectional"))
      (node (ref "L2") (pin "2") (pinfunction "2_2") (pintype "bidirectional"))
    )
    (net (code "16") (name "Net-(D8-K)") (class "Default")
      (node (ref "D8") (pin "1") (pinfunction "K_1") (pintype "bidirectional"))
      (node (ref "D9") (pin "2") (pinfunction "A_2") (pintype "bidirectional"))
    )
    (net (code "17") (name "Net-(D9-K)") (class "Default")
      (node (ref "C33") (pin "2") (pinfunction "2_2") (pintype "passive"))
      (node (ref "D9") (pin "1") (pinfunction "K_1") (pintype "bidirectional"))
      (node (ref "PS2") (pin "3") (pinfunction "_+VIN_3") (pintype "bidirectional"))
    )
    (net (code "18") (name "Net-(HVLED-PadA)") (class "Default")
      (node (ref "HVLED") (pin "A") (pinfunction "A_A") (pintype "passive"))
      (node (ref "R36") (pin "1") (pinfunction "1_1") (pintype "passive"))
    )
    (net (code "19") (name "Net-(IC1-CS)") (class "Default")
      (node (ref "C14") (pin "1") (pinfunction "1_1") (pintype "passive"))
      (node (ref "IC1") (pin "3") (pinfunction "CS_3") (pintype "bidirectional"))
      (node (ref "R11") (pin "1") (pinfunction "1_1") (pintype "passive"))
    )
    (net (code "20") (name "Net-(IC1-ISET)") (class "Default")
      (node (ref "IC1") (pin "2") (pinfunction "ISET_2") (pintype "bidirectional"))
      (node (ref "R12") (pin "1") (pinfunction "1_1") (pintype "passive"))
    )
    (net (code "21") (name "Net-(IC1-OUTA)") (class "Default")
      (node (ref "IC1") (pin "7") (pinfunction "OUTA_7") (pintype "bidirectional"))
      (node (ref "IC2") (pin "2") (pinfunction "INA_2") (pintype "bidirectional"))
    )
    (net (code "22") (name "Net-(IC1-OUTB)") (class "Default")
      (node (ref "IC1") (pin "6") (pinfunction "OUTB_6") (pintype "bidirectional"))
      (node (ref "IC2") (pin "4") (pinfunction "INB_4") (pintype "bidirectional"))
    )
    (net (code "23") (name "Net-(IC1-RT)") (class "Default")
      (node (ref "IC1") (pin "4") (pinfunction "RT_4") (pintype "bidirectional"))
      (node (ref "R13") (pin "1") (pinfunction "1_1") (pintype "passive"))
    )
    (net (code "24") (name "Net-(IC2-ENA)") (class "Default")
      (node (ref "IC2") (pin "1") (pinfunction "ENA_1") (pintype "bidirectional"))
      (node (ref "IC2") (pin "8") (pinfunction "ENB_8") (pintype "bidirectional"))
      (node (ref "R2") (pin "1") (pinfunction "1_1") (pintype "passive"))
    )
    (net (code "25") (name "Net-(IC2-OUT1)") (class "Default")
      (node (ref "IC2") (pin "7") (pinfunction "OUT1_7") (pintype "bidirectional"))
      (node (ref "R3") (pin "1") (pinfunction "1_1") (pintype "passive"))
      (node (ref "R4") (pin "1") (pinfunction "1_1") (pintype "passive"))
    )
    (net (code "26") (name "Net-(IC2-OUT2)") (class "Default")
      (node (ref "IC2") (pin "5") (pinfunction "OUT2_5") (pintype "bidirectional"))
      (node (ref "R5") (pin "1") (pinfunction "1_1") (pintype "passive"))
      (node (ref "R6") (pin "1") (pinfunction "1_1") (pintype "passive"))
    )
    (net (code "27") (name "Net-(IC4-BS)") (class "Default")
      (node (ref "C8") (pin "1") (pinfunction "1_1") (pintype "passive"))
      (node (ref "IC4") (pin "1") (pinfunction "BS_1") (pintype "bidirectional"))
    )
    (net (code "28") (name "Net-(IC4-EN)") (class "Default")
      (node (ref "IC4") (pin "4") (pinfunction "EN_4") (pintype "bidirectional"))
      (node (ref "R28") (pin "2") (pinfunction "2_2") (pintype "passive"))
    )
    (net (code "29") (name "Net-(IC4-FB)") (class "Default")
      (node (ref "C12") (pin "2") (pinfunction "2_2") (pintype "passive"))
      (node (ref "IC4") (pin "3") (pinfunction "FB_3") (pintype "bidirectional"))
      (node (ref "R29") (pin "2") (pinfunction "2_2") (pintype "passive"))
      (node (ref "R30") (pin "1") (pinfunction "1_1") (pintype "passive"))
    )
    (net (code "30") (name "Net-(IC6-CATHODE)") (class "Default")
      (node (ref "C20") (pin "2") (pinfunction "2_2") (pintype "passive"))
      (node (ref "IC6") (pin "1") (pinfunction "CATHODE_1") (pintype "bidirectional"))
      (node (ref "OPT1") (pin "2") (pinfunction "K_2") (pintype "bidirectional"))
      (node (ref "R15") (pin "1") (pinfunction "1_1") (pintype "passive"))
    )
    (net (code "31") (name "Net-(IC6-REF)") (class "Default")
      (node (ref "C20") (pin "1") (pinfunction "1_1") (pintype "passive"))
      (node (ref "C21") (pin "1") (pinfunction "1_1") (pintype "passive"))
      (node (ref "IC6") (pin "2") (pinfunction "REF_2") (pintype "bidirectional"))
      (node (ref "J1") (pin "1") (pinfunction "1_1") (pintype "passive"))
      (node (ref "R14") (pin "2") (pinfunction "2_2") (pintype "passive"))
      (node (ref "R16") (pin "2") (pinfunction "2_2") (pintype "passive"))
    )
    (net (code "32") (name "Net-(IC7-BS)") (class "Default")
      (node (ref "C27") (pin "2") (pinfunction "2_2") (pintype "passive"))
      (node (ref "IC7") (pin "1") (pinfunction "BS_1") (pintype "bidirectional"))
    )
    (net (code "33") (name "Net-(IC7-EN)") (class "Default")
      (node (ref "IC7") (pin "4") (pinfunction "EN_4") (pintype "bidirectional"))
      (node (ref "R26") (pin "2") (pinfunction "2_2") (pintype "passive"))
    )
    (net (code "34") (name "Net-(IC7-FB)") (class "Default")
      (node (ref "C30") (pin "2") (pinfunction "2_2") (pintype "passive"))
      (node (ref "IC7") (pin "3") (pinfunction "FB_3") (pintype "bidirectional"))
      (node (ref "R25") (pin "1") (pinfunction "1_1") (pintype "passive"))
      (node (ref "R27") (pin "1") (pinfunction "1_1") (pintype "passive"))
    )
    (net (code "35") (name "Net-(OPT1-A)") (class "Default")
      (node (ref "OPT1") (pin "1") (pinfunction "A_1") (pintype "bidirectional"))
      (node (ref "R17") (pin "2") (pinfunction "2_2") (pintype "passive"))
    )
    (net (code "36") (name "Net-(Q1-G)") (class "Default")
      (node (ref "GATE1_TP") (pin "TP") (pinfunction "TP_TP") (pintype "input"))
      (node (ref "Q1") (pin "1") (pinfunction "G_1") (pintype "bidirectional"))
      (node (ref "R3") (pin "2") (pinfunction "2_2") (pintype "passive"))
      (node (ref "R4") (pin "2") (pinfunction "2_2") (pintype "passive"))
    )
    (net (code "37") (name "Net-(Q2-G)") (class "Default")
      (node (ref "GATE2_TP") (pin "TP") (pinfunction "TP_TP") (pintype "input"))
      (node (ref "Q2") (pin "1") (pinfunction "G_1") (pintype "bidirectional"))
      (node (ref "R5") (pin "2") (pinfunction "2_2") (pintype "passive"))
      (node (ref "R6") (pin "2") (pinfunction "2_2") (pintype "passive"))
    )
    (net (code "38") (name "Net-(R10-Pad1)") (class "Default")
      (node (ref "R10") (pin "1") (pinfunction "1_1") (pintype "passive"))
      (node (ref "R9") (pin "2") (pinfunction "2_2") (pintype "passive"))
    )
    (net (code "39") (name "Net-(R10-Pad2)") (class "Default")
      (node (ref "R10") (pin "2") (pinfunction "2_2") (pintype "passive"))
      (node (ref "R14") (pin "1") (pinfunction "1_1") (pintype "passive"))
    )
    (net (code "40") (name "Net-(R16-Pad1)") (class "Default")
      (node (ref "R16") (pin "1") (pinfunction "1_1") (pintype "passive"))
      (node (ref "R18") (pin "2") (pinfunction "2_2") (pintype "passive"))
    )
    (net (code "41") (name "Net-(R19-Pad1)") (class "Default")
      (node (ref "R19") (pin "1") (pinfunction "1_1") (pintype "passive"))
      (node (ref "R36") (pin "2") (pinfunction "2_2") (pintype "passive"))
    )
    (net (code "42") (name "Net-(R19-Pad2)") (class "Default")
      (node (ref "R19") (pin "2") (pinfunction "2_2") (pintype "passive"))
      (node (ref "R22") (pin "1") (pinfunction "1_1") (pintype "passive"))
    )
    (net (code "43") (name "Net-(R22-Pad2)") (class "Default")
      (node (ref "R22") (pin "2") (pinfunction "2_2") (pintype "passive"))
      (node (ref "R34") (pin "1") (pinfunction "1_1") (pintype "passive"))
    )
    (net (code "44") (name "Net-(R34-Pad2)") (class "Default")
      (node (ref "R34") (pin "2") (pinfunction "2_2") (pintype "passive"))
      (node (ref "R35") (pin "1") (pinfunction "1_1") (pintype "passive"))
    )
    (net (code "45") (name "Net-(SJ1-Pad1)") (class "Default")
      (node (ref "SJ1") (pin "1") (pinfunction "1_1") (pintype "passive"))
      (node (ref "T1") (pin "11") (pinfunction "11_11") (pintype "bidirectional"))
    )
    (net (code "46") (name "Net-(SJ1-Pad3)") (class "Default")
      (node (ref "SJ1") (pin "3") (pinfunction "3_3") (pintype "passive"))
      (node (ref "T1") (pin "13") (pinfunction "13_13") (pintype "bidirectional"))
    )
    (net (code "47") (name "Net-(VR1-ADJ)") (class "Default")
      (node (ref "R20") (pin "1") (pinfunction "1_1") (pintype "passive"))
      (node (ref "R21") (pin "2") (pinfunction "2_2") (pintype "passive"))
      (node (ref "VR1") (pin "1") (pinfunction "ADJ_1") (pintype "input"))
    )
    (net (code "48") (name "OPTO-EMITT") (class "Default")
      (node (ref "IC1") (pin "1") (pinfunction "CTRL_1") (pintype "bidirectional"))
      (node (ref "OPT1") (pin "4") (pinfunction "C_4") (pintype "bidirectional"))
      (node (ref "R1") (pin "2") (pinfunction "2_2") (pintype "passive"))
    )
    (net (code "49") (name "PRE") (class "Default")
      (node (ref "C26") (pin "2") (pinfunction "2_2") (pintype "passive"))
      (node (ref "C28") (pin "2") (pinfunction "2_2") (pintype "passive"))
      (node (ref "C29") (pin "2") (pinfunction "2_2") (pintype "passive"))
      (node (ref "C30") (pin "1") (pinfunction "1_1") (pintype "passive"))
      (node (ref "L1") (pin "2") (pinfunction "2_2") (pintype "bidirectional"))
      (node (ref "MAINBUCK_TP") (pin "TP") (pinfunction "TP_TP") (pintype "input"))
      (node (ref "R25") (pin "2") (pinfunction "2_2") (pintype "passive"))
      (node (ref "VR1") (pin "3") (pinfunction "IN_3") (pintype "input"))
    )
    (net (code "50") (name "PWRGND") (class "Default")
      (node (ref "C10") (pin "1") (pinfunction "1_1") (pintype "passive"))
      (node (ref "C11") (pin "1") (pinfunction "1_1") (pintype "passive"))
      (node (ref "C15") (pin "2") (pinfunction "-_2") (pintype "bidirectional"))
      (node (ref "C16") (pin "2") (pinfunction "-_2") (pintype "bidirectional"))
      (node (ref "C17") (pin "2") (pinfunction "2_2") (pintype "bidirectional"))
      (node (ref "C18") (pin "2") (pinfunction "2_2") (pintype "bidirectional"))
      (node (ref "C25") (pin "1") (pinfunction "1_1") (pintype "passive"))
      (node (ref "C31") (pin "1") (pinfunction "1_1") (pintype "passive"))
      (node (ref "C34") (pin "1") (pinfunction "1_1") (pintype "passive"))
      (node (ref "C7") (pin "2") (pinfunction "2_2") (pintype "passive"))
      (node (ref "C9") (pin "2") (pinfunction "2_2") (pintype "passive"))
      (node (ref "D1") (pin "1") (pinfunction "A1_1") (pintype "bidirectional"))
      (node (ref "D1") (pin "3") (pinfunction "A2_3") (pintype "bidirectional"))
      (node (ref "D4") (pin "1") (pinfunction "A1_1") (pintype "bidirectional"))
      (node (ref "D4") (pin "3") (pinfunction "A2_3") (pintype "bidirectional"))
      (node (ref "D7") (pin "2") (pinfunction "A_2") (pintype "bidirectional"))
      (node (ref "HVLED") (pin "C") (pinfunction "C_C") (pintype "passive"))
      (node (ref "IC4") (pin "2") (pinfunction "GND_2") (pintype "bidirectional"))
      (node (ref "IC6") (pin "3") (pinfunction "ANODE_3") (pintype "bidirectional"))
      (node (ref "J1") (pin "2") (pinfunction "2_2") (pintype "passive"))
      (node (ref "J3") (pin "1") (pinfunction "1_1") (pintype "bidirectional"))
      (node (ref "PS2") (pin "7") (pinfunction "-VOUT_7") (pintype "bidirectional"))
      (node (ref "PWRGND_TP") (pin "TP") (pinfunction "TP_TP") (pintype "input"))
      (node (ref "R18") (pin "1") (pinfunction "1_1") (pintype "passive"))
      (node (ref "R30") (pin "2") (pinfunction "2_2") (pintype "passive"))
      (node (ref "R32") (pin "1") (pinfunction "1_1") (pintype "passive"))
      (node (ref "T1") (pin "15") (pinfunction "15_15") (pintype "bidirectional"))
      (node (ref "T1.2") (pin "4") (pinfunction "4_4") (pintype "bidirectional"))
      (node (ref "VR2") (pin "1") (pinfunction "GND_1") (pintype "bidirectional"))
      (node (ref "Z3") (pin "2") (pinfunction "A_2") (pintype "bidirectional"))
    )
    (net (code "51") (name "RECT") (class "Default")
      (node (ref "D2") (pin "2") (pinfunction "K_2") (pintype "bidirectional"))
      (node (ref "D3") (pin "2") (pinfunction "K_2") (pintype "bidirectional"))
      (node (ref "L3") (pin "1") (pinfunction "1_1") (pintype "bidirectional"))
    )
    (net (code "52") (name "REG") (class "Default")
      (node (ref "13.75V") (pin "A") (pinfunction "A_A") (pintype "passive"))
      (node (ref "13.75V_TP") (pin "TP") (pinfunction "TP_TP") (pintype "input"))
      (node (ref "C1") (pin "1") (pinfunction "1_1") (pintype "passive"))
      (node (ref "C13") (pin "1") (pinfunction "1_1") (pintype "passive"))
      (node (ref "C2") (pin "1") (pinfunction "1_1") (pintype "passive"))
      (node (ref "C22") (pin "2") (pinfunction "2_2") (pintype "passive"))
      (node (ref "C32") (pin "2") (pinfunction "2_2") (pintype "passive"))
      (node (ref "D8") (pin "2") (pinfunction "A_2") (pintype "bidirectional"))
      (node (ref "IC1") (pin "8") (pinfunction "VDD_8") (pintype "bidirectional"))
      (node (ref "IC2") (pin "6") (pinfunction "VDD_6") (pintype "bidirectional"))
      (node (ref "R1") (pin "1") (pinfunction "1_1") (pintype "passive"))
      (node (ref "R2") (pin "2") (pinfunction "2_2") (pintype "passive"))
      (node (ref "R20") (pin "2") (pinfunction "2_2") (pintype "passive"))
      (node (ref "VR1") (pin "4") (pinfunction "OUT_4") (pintype "passive"))
    )
    (net (code "53") (name "REG5V") (class "Default")
      (node (ref "5VLED") (pin "A") (pinfunction "A_A") (pintype "passive"))
      (node (ref "AUX5V_TP") (pin "TP") (pinfunction "TP_TP") (pintype "input"))
      (node (ref "C11") (pin "2") (pinfunction "2_2") (pintype "passive"))
      (node (ref "C34") (pin "2") (pinfunction "2_2") (pintype "passive"))
      (node (ref "PS2") (pin "8") (pinfunction "+VOUT_8") (pintype "bidirectional"))
      (node (ref "R17") (pin "1") (pinfunction "1_1") (pintype "passive"))
      (node (ref "VR2") (pin "2") (pinfunction "VOUT_2") (pintype "bidirectional"))
    )
    (net (code "54") (name "TRANS1") (class "Default")
      (node (ref "D3") (pin "1") (pinfunction "A1_1") (pintype "bidirectional"))
      (node (ref "D3") (pin "3") (pinfunction "A2_3") (pintype "bidirectional"))
      (node (ref "D4") (pin "2") (pinfunction "K_2") (pintype "bidirectional"))
      (node (ref "SJ1") (pin "2") (pinfunction "2_2") (pintype "passive"))
      (node (ref "T1.2") (pin "8") (pinfunction "8_8") (pintype "bidirectional"))
    )
    (net (code "55") (name "TRANS2") (class "Default")
      (node (ref "D1") (pin "2") (pinfunction "K_2") (pintype "bidirectional"))
      (node (ref "D2") (pin "1") (pinfunction "A1_1") (pintype "bidirectional"))
      (node (ref "D2") (pin "3") (pinfunction "A2_3") (pintype "bidirectional"))
      (node (ref "T1") (pin "9") (pinfunction "9_9") (pintype "bidirectional"))
      (node (ref "T1.2") (pin "14") (pinfunction "14_14") (pintype "bidirectional"))
    )
    (net (code "56") (name "VCC28V") (class "Default")
      (node (ref "C23") (pin "2") (pinfunction "2_2") (pintype "passive"))
      (node (ref "C24") (pin "1") (pinfunction "1_1") (pintype "passive"))
      (node (ref "C3") (pin "1") (pinfunction "+_1") (pintype "bidirectional"))
      (node (ref "C35") (pin "1") (pinfunction "1_1") (pintype "passive"))
      (node (ref "C4") (pin "1") (pinfunction "+_1") (pintype "bidirectional"))
      (node (ref "C5") (pin "1") (pinfunction "+_1") (pintype "bidirectional"))
      (node (ref "C6") (pin "1") (pinfunction "+_1") (pintype "bidirectional"))
      (node (ref "IC7") (pin "5") (pinfunction "IN_5") (pintype "bidirectional"))
      (node (ref "J2") (pin "1") (pinfunction "1_1") (pintype "bidirectional"))
      (node (ref "R26") (pin "1") (pinfunction "1_1") (pintype "passive"))
      (node (ref "T1") (pin "4") (pinfunction "4_4") (pintype "bidirectional"))
      (node (ref "T1") (pin "5") (pinfunction "5_5") (pintype "bidirectional"))
      (node (ref "T1.2") (pin "7") (pinfunction "7_7") (pintype "bidirectional"))
    )
    (net (code "57") (name "unconnected-(PS2-NA-Pad14)") (class "Default")
      (node (ref "PS2") (pin "14") (pinfunction "NA_14") (pintype "bidirectional"))
    )
    (net (code "58") (name "unconnected-(T1-Pad3)") (class "Default")
      (node (ref "T1") (pin "3") (pinfunction "3_3") (pintype "bidirectional"))
    )
    (net (code "59") (name "unconnected-(T1-Pad6)") (class "Default")
      (node (ref "T1") (pin "6") (pinfunction "6_6") (pintype "bidirectional"))
    )
    (net (code "60") (name "unconnected-(T1-Pad10)") (class "Default")
      (node (ref "T1") (pin "10") (pinfunction "10_10") (pintype "bidirectional"))
    )
    (net (code "61") (name "unconnected-(T1-Pad12)") (class "Default")
      (node (ref "T1") (pin "12") (pinfunction "12_12") (pintype "bidirectional"))
    )
    (net (code "62") (name "unconnected-(T1-Pad14)") (class "Default")
      (node (ref "T1") (pin "14") (pinfunction "14_14") (pintype "bidirectional"))
    )
    (net (code "63") (name "unconnected-(T1.2-Pad5)") (class "Default")
      (node (ref "T1.2") (pin "5") (pinfunction "5_5") (pintype "bidirectional"))
    )
    (net (code "64") (name "unconnected-(T1.2-Pad6)") (class "Default")
      (node (ref "T1.2") (pin "6") (pinfunction "6_6") (pintype "bidirectional"))
    )
    (net (code "65") (name "unconnected-(T1.2-Pad9)") (class "Default")
      (node (ref "T1.2") (pin "9") (pinfunction "9_9") (pintype "bidirectional"))
    )
    (net (code "66") (name "unconnected-(T1.2-Pad10)") (class "Default")
      (node (ref "T1.2") (pin "10") (pinfunction "10_10") (pintype "bidirectional"))
    )
    (net (code "67") (name "unconnected-(T1.2-Pad12)") (class "Default")
      (node (ref "T1.2") (pin "12") (pinfunction "12_12") (pintype "bidirectional"))
    )
  )
)
